# Schema.net
KiCad netlist of a schematic drawn in Altium Designer
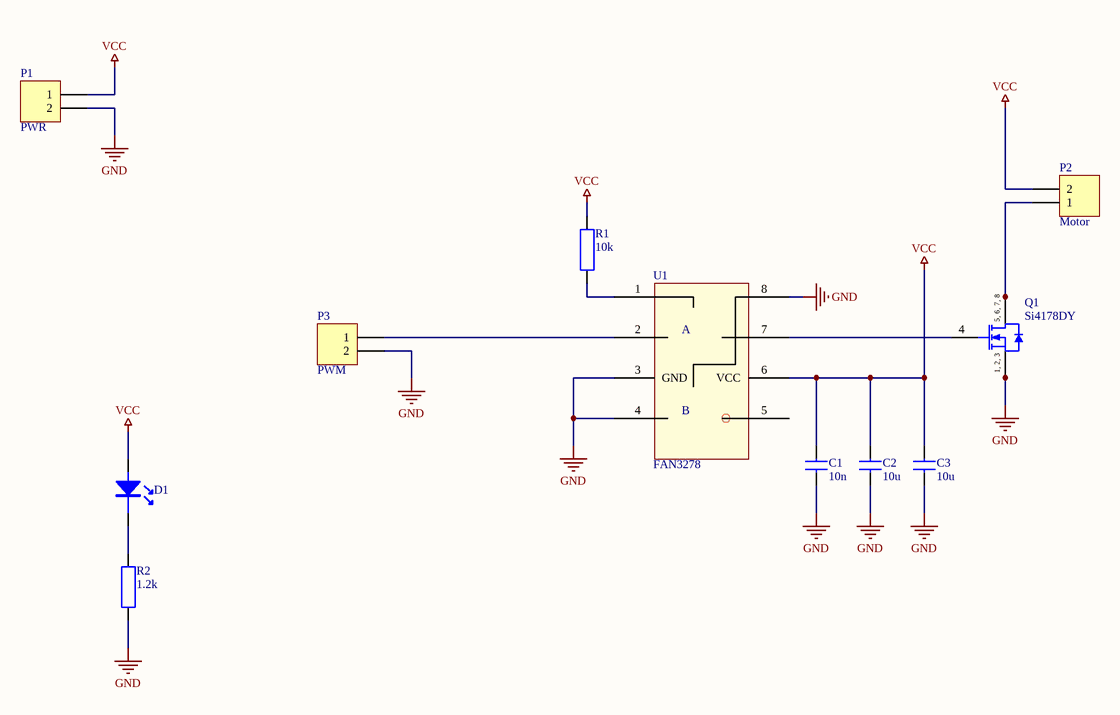
[diagram p0: Schema.SchDoc]

(export (version "E")
  (design (tool "Eeschema 10.0.6"))
  (components
    (comp (ref "C1")
      (value "10n")
      (footprint "0805")
      (description "Normaler Kondensator")
      (libsource (lib "DEVICE_HSLU") (part "C?"))
    )
    (comp (ref "C2")
      (value "10u")
      (footprint "1206")
      (description "Normaler Kondensator")
      (libsource (lib "DC-Ansteuerung") (part "C?"))
    )
    (comp (ref "C3")
      (value "10u")
      (footprint "1206")
      (description "Normaler Kondensator")
      (libsource (lib "DC-Ansteuerung") (part "C?"))
    )
    (comp (ref "D1") (value "LED") (footprint "0805") (libsource (lib "BLDC_Board_Library") (part "LED")))
    (comp (ref "P1")
      (value "PWR")
      (footprint "Stecker_1x2_200mil")
      (description "Header, 2-Pin")
      (fields (field (name "PUBLISHER") "Altium Limited"))
      (libsource (lib "BLDC_Board_Library") (part "Header 2"))
    )
    (comp (ref "P2")
      (value "Motor")
      (footprint "Stecker_1x2_200mil")
      (description "Header, 2-Pin")
      (fields (field (name "PUBLISHER") "Altium Limited"))
      (libsource (lib "") (part "Header 2_1"))
    )
    (comp (ref "P3")
      (value "PWM")
      (footprint "HDR1X2")
      (description "Header, 2-Pin")
      (fields (field (name "PUBLISHER") "Altium Limited"))
      (libsource (lib "Miscellaneous Connectors") (part "Header 2"))
    )
    (comp (ref "Q1")
      (value "Si4178DY")
      (footprint "SO-8_L")
      (description "N-Channel 30V (D-S)  Rated MOSFET")
      (fields (field (name "PUBLISHER") "Altium Limited"))
      (libsource (lib "DC-Ansteuerung") (part "SI4412DY"))
    )
    (comp (ref "R1")
      (value "10k")
      (footprint "0805")
      (description "Normaler Widerstand")
      (libsource (lib "DEVICE_HSLU") (part "R?"))
    )
    (comp (ref "R2")
      (value "1.2k")
      (footprint "0805")
      (description "Normaler Widerstand")
      (libsource (lib "DEVICE_HSLU") (part "R?"))
    )
    (comp (ref "U1")
      (value "FAN3278")
      (footprint "SO-8_L")
      (libsource (lib "DC-Ansteuerung") (part "FAN3278"))
    )
  )
  (nets
    (net (code "1") (name "GND") (class "Default")
      (node (ref "C1") (pin "2") (pinfunction "2_2") (pintype "passive"))
      (node (ref "C2") (pin "2") (pinfunction "2_2") (pintype "passive"))
      (node (ref "C3") (pin "2") (pinfunction "2_2") (pintype "passive"))
      (node (ref "P1") (pin "2") (pinfunction "2_2") (pintype "passive"))
      (node (ref "P3") (pin "2") (pinfunction "2_2") (pintype "passive"))
      (node (ref "Q1") (pin "1") (pinfunction "S_1") (pintype "passive"))
      (node (ref "Q1") (pin "2") (pinfunction "S_2") (pintype "passive"))
      (node (ref "Q1") (pin "3") (pinfunction "S_3") (pintype "passive"))
      (node (ref "R2") (pin "1") (pintype "passive"))
      (node (ref "U1") (pin "3") (pinfunction "GND_3") (pintype "passive"))
      (node (ref "U1") (pin "4") (pinfunction "4_4") (pintype "passive"))
      (node (ref "U1") (pin "8") (pinfunction "8_8") (pintype "passive"))
    )
    (net (code "2") (name "Net-(D1-Pad1)") (class "Default")
      (node (ref "D1") (pin "1") (pintype "passive"))
      (node (ref "R2") (pin "2") (pintype "passive"))
    )
    (net (code "3") (name "Net-(P2-Pad1)") (class "Default")
      (node (ref "P2") (pin "1") (pinfunction "1_1") (pintype "passive"))
      (node (ref "Q1") (pin "5") (pinfunction "D_5") (pintype "passive"))
      (node (ref "Q1") (pin "6") (pinfunction "D_6") (pintype "passive"))
      (node (ref "Q1") (pin "7") (pinfunction "D_7") (pintype "passive"))
      (node (ref "Q1") (pin "8") (pinfunction "D_8") (pintype "passive"))
    )
    (net (code "4") (name "Net-(P3-Pad1)") (class "Default")
      (node (ref "P3") (pin "1") (pinfunction "1_1") (pintype "passive"))
      (node (ref "U1") (pin "2") (pinfunction "2_2") (pintype "passive"))
    )
    (net (code "5") (name "Net-(Q1-G)") (class "Default")
      (node (ref "Q1") (pin "4") (pinfunction "G_4") (pintype "passive"))
      (node (ref "U1") (pin "7") (pinfunction "7_7") (pintype "passive"))
    )
    (net (code "6") (name "Net-(R1-Pad1)") (class "Default")
      (node (ref "R1") (pin "1") (pintype "passive"))
      (node (ref "U1") (pin "1") (pinfunction "1_1") (pintype "passive"))
    )
    (net (code "7") (name "VCC") (class "Default")
      (node (ref "C1") (pin "1") (pinfunction "1_1") (pintype "passive"))
      (node (ref "C2") (pin "1") (pinfunction "1_1") (pintype "passive"))
      (node (ref "C3") (pin "1") (pinfunction "1_1") (pintype "passive"))
      (node (ref "D1") (pin "2") (pintype "passive"))
      (node (ref "P1") (pin "1") (pinfunction "1_1") (pintype "passive"))
      (node (ref "P2") (pin "2") (pinfunction "2_2") (pintype "passive"))
      (node (ref "R1") (pin "2") (pintype "passive"))
      (node (ref "U1") (pin "6") (pinfunction "VCC_6") (pintype "passive"))
    )
    (net (code "8") (name "unconnected-(U1-Pad5)") (class "Default")
      (node (ref "U1") (pin "5") (pinfunction "5_5") (pintype "passive"))
    )
  )
)
